# switch.net
KiCad netlist of a schematic drawn in Altium Designer
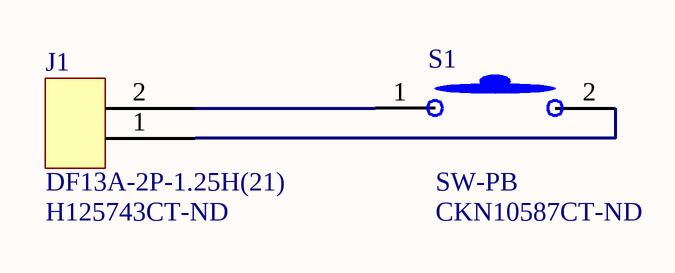
[diagram p0: switch.SchDoc]

(export (version "E")
  (design (tool "Eeschema 10.0.6"))
  (components
    (comp (ref "J1")
      (value "DF13A-2P-1.25H(21)")
      (footprint "DF13A-2P-1.25H(21)")
      (description "2 pos DF13 right angle surface mount connector")
      (fields (field (name "SUPPLIER PART NUMBER 1") "H125743CT-ND"))
      (libsource (lib "heron-general") (part "DF13A-2P-1.25H(21)"))
    )
    (comp (ref "S1")
      (value "SW-PB")
      (footprint "PTS830GM140 SMTR LFS - Pushbutton")
      (description "Schematic symbol for a generic 2-pin pushbutton, OFF-mom.")
      (fields (field (name "SUPPLIER PART NUMBER 1") "CKN10587CT-ND"))
      (libsource (lib "heron-general") (part "Pushbutton - Low Profile"))
    )
  )
  (nets
    (net (code "1") (name "Net-(J1-Pad1)") (class "Default")
      (node (ref "J1") (pin "1") (pintype "passive"))
      (node (ref "S1") (pin "2") (pinfunction "2_2") (pintype "passive"))
    )
    (net (code "2") (name "Net-(J1-Pad2)") (class "Default")
      (node (ref "J1") (pin "2") (pintype "passive"))
      (node (ref "S1") (pin "1") (pinfunction "1_1") (pintype "passive"))
    )
  )
)
